# Joy2PS2_mini_v3.net
KiCad netlist of a schematic drawn in EAGLE
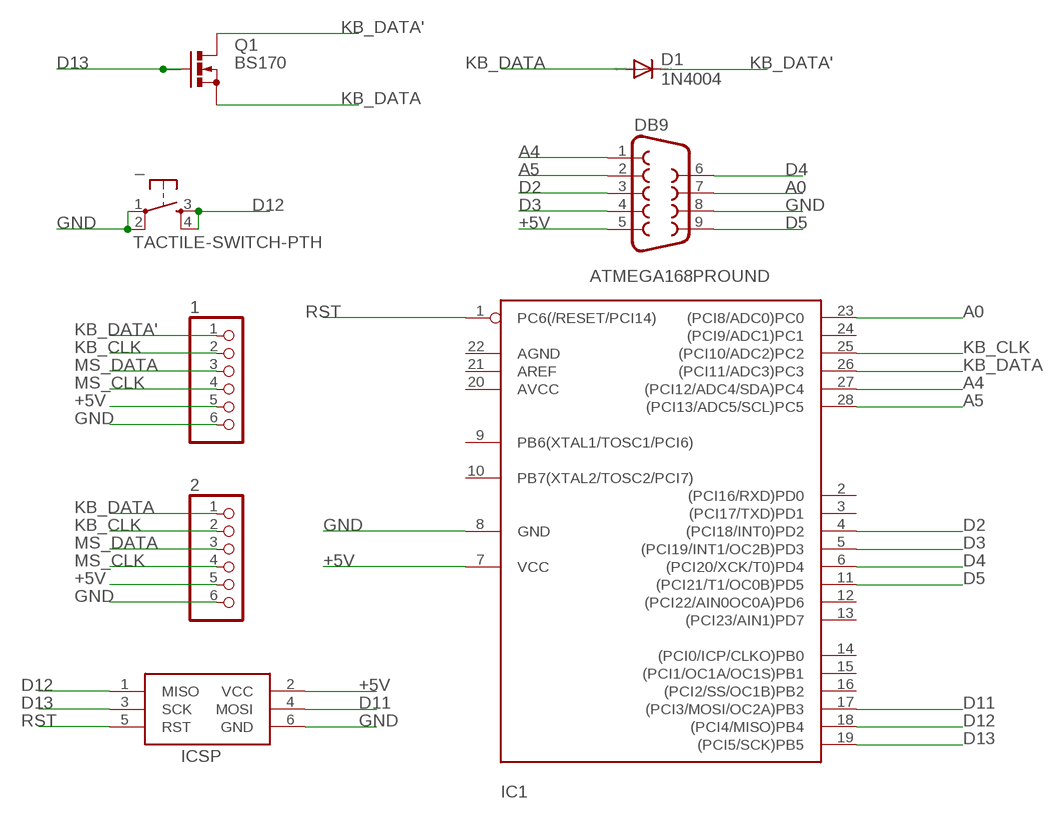
[diagram p0: schematic, sheet 1]

(export (version "E")
  (design (tool "Eeschema 10.0.6"))
  (components
    (comp (ref "1")
      (value "PINHD-1X6")
      (footprint "eagle-import:1X06")
      (libsource (lib "eagle-import") (part "PINHD-1X6"))
    )
    (comp (ref "2")
      (value "PINHD-1X6")
      (footprint "eagle-import:1X06")
      (libsource (lib "eagle-import") (part "PINHD-1X6"))
    )
    (comp (ref "D1")
      (value "1N4004")
      (footprint "eagle-import:DO41-10")
      (libsource (lib "eagle-import") (part "1N4004"))
    )
    (comp (ref "DB9")
      (value "DB9MALE")
      (footprint "eagle-import:DB9_MALE")
      (libsource (lib "eagle-import") (part "DB9MALE"))
    )
    (comp (ref "IC1")
      (value "ATMEGA168PROUND")
      (footprint "eagle-import:DIL28-3-ROUND")
      (libsource (lib "eagle-import") (part "ATMEGA168PROUND"))
    )
    (comp (ref "ICSP")
      (value "AVRISP-6")
      (footprint "eagle-import:AVRISP")
      (libsource (lib "eagle-import") (part "AVRISP-6"))
    )
    (comp (ref "Q1")
      (value "BS170")
      (footprint "eagle-import:SOT54E")
      (libsource (lib "eagle-import") (part "BS170"))
    )
    (comp (ref "_")
      (value "TACTILE-SWITCH-PTH")
      (footprint "eagle-import:TAC-SWITCH-PTH")
      (libsource (lib "eagle-import") (part "TACTILE-SWITCH-PTH"))
    )
  )
  (nets
    (net (code "1") (name "/+5V") (class "Default")
      (node (ref "1") (pin "5") (pinfunction "5_5") (pintype "passive"))
      (node (ref "2") (pin "5") (pinfunction "5_5") (pintype "passive"))
      (node (ref "DB9") (pin "5") (pinfunction "5_5") (pintype "passive"))
      (node (ref "IC1") (pin "7") (pinfunction "VCC_7") (pintype "bidirectional"))
      (node (ref "ICSP") (pin "2") (pinfunction "VCC_2") (pintype "power_in"))
    )
    (net (code "2") (name "/A0") (class "Default")
      (node (ref "DB9") (pin "7") (pinfunction "7_7") (pintype "passive"))
      (node (ref "IC1") (pin "23") (pinfunction "(PCI8/ADC0)PC0_23") (pintype "bidirectional"))
    )
    (net (code "3") (name "/A4") (class "Default")
      (node (ref "DB9") (pin "1") (pinfunction "1_1") (pintype "passive"))
      (node (ref "IC1") (pin "27") (pinfunction "(PCI12/ADC4/SDA)PC4_27") (pintype "bidirectional"))
    )
    (net (code "4") (name "/A5") (class "Default")
      (node (ref "DB9") (pin "2") (pinfunction "2_2") (pintype "passive"))
      (node (ref "IC1") (pin "28") (pinfunction "(PCI13/ADC5/SCL)PC5_28") (pintype "bidirectional"))
    )
    (net (code "5") (name "/D2") (class "Default")
      (node (ref "DB9") (pin "3") (pinfunction "3_3") (pintype "passive"))
      (node (ref "IC1") (pin "4") (pinfunction "(PCI18/INT0)PD2_4") (pintype "bidirectional"))
    )
    (net (code "6") (name "/D3") (class "Default")
      (node (ref "DB9") (pin "4") (pinfunction "4_4") (pintype "passive"))
      (node (ref "IC1") (pin "5") (pinfunction "(PCI19/INT1/OC2B)PD3_5") (pintype "bidirectional"))
    )
    (net (code "7") (name "/D4") (class "Default")
      (node (ref "DB9") (pin "6") (pinfunction "6_6") (pintype "passive"))
      (node (ref "IC1") (pin "6") (pinfunction "(PCI20/XCK/T0)PD4_6") (pintype "bidirectional"))
    )
    (net (code "8") (name "/D5") (class "Default")
      (node (ref "DB9") (pin "9") (pinfunction "9_9") (pintype "passive"))
      (node (ref "IC1") (pin "11") (pinfunction "(PCI21/T1/OC0B)PD5_11") (pintype "bidirectional"))
    )
    (net (code "9") (name "/D11") (class "Default")
      (node (ref "IC1") (pin "17") (pinfunction "(PCI3/MOSI/OC2A)PB3_17") (pintype "bidirectional"))
      (node (ref "ICSP") (pin "4") (pinfunction "MOSI_4") (pintype "output"))
    )
    (net (code "10") (name "/D12") (class "Default")
      (node (ref "IC1") (pin "18") (pinfunction "(PCI4/MISO)PB4_18") (pintype "bidirectional"))
      (node (ref "ICSP") (pin "1") (pinfunction "MISO_1") (pintype "input"))
      (node (ref "_") (pin "3") (pinfunction "3_3") (pintype "passive"))
      (node (ref "_") (pin "4") (pinfunction "4_4") (pintype "passive"))
    )
    (net (code "11") (name "/D13") (class "Default")
      (node (ref "IC1") (pin "19") (pinfunction "(PCI5/SCK)PB5_19") (pintype "bidirectional"))
      (node (ref "ICSP") (pin "3") (pinfunction "SCK_3") (pintype "output"))
      (node (ref "Q1") (pin "G") (pinfunction "G_G") (pintype "passive"))
    )
    (net (code "12") (name "/GND") (class "Default")
      (node (ref "1") (pin "6") (pinfunction "6_6") (pintype "passive"))
      (node (ref "2") (pin "6") (pinfunction "6_6") (pintype "passive"))
      (node (ref "DB9") (pin "8") (pinfunction "8_8") (pintype "passive"))
      (node (ref "IC1") (pin "8") (pinfunction "GND_8") (pintype "bidirectional"))
      (node (ref "ICSP") (pin "6") (pinfunction "GND_6") (pintype "power_in"))
      (node (ref "_") (pin "1") (pinfunction "1_1") (pintype "passive"))
      (node (ref "_") (pin "2") (pinfunction "2_2") (pintype "passive"))
    )
    (net (code "13") (name "/KB_CLK") (class "Default")
      (node (ref "1") (pin "2") (pinfunction "2_2") (pintype "passive"))
      (node (ref "2") (pin "2") (pinfunction "2_2") (pintype "passive"))
      (node (ref "IC1") (pin "25") (pinfunction "(PCI10/ADC2)PC2_25") (pintype "bidirectional"))
    )
    (net (code "14") (name "/KB_DATA") (class "Default")
      (node (ref "2") (pin "1") (pinfunction "1_1") (pintype "passive"))
      (node (ref "D1") (pin "A") (pinfunction "A_A") (pintype "passive"))
      (node (ref "IC1") (pin "26") (pinfunction "(PCI11/ADC3)PC3_26") (pintype "bidirectional"))
      (node (ref "Q1") (pin "S") (pinfunction "S_S") (pintype "passive"))
    )
    (net (code "15") (name "/KB_DATA'") (class "Default")
      (node (ref "1") (pin "1") (pinfunction "1_1") (pintype "passive"))
      (node (ref "D1") (pin "C") (pinfunction "C_C") (pintype "passive"))
      (node (ref "Q1") (pin "D") (pinfunction "D_D") (pintype "passive"))
    )
    (net (code "16") (name "/MS_CLK") (class "Default")
      (node (ref "1") (pin "4") (pinfunction "4_4") (pintype "passive"))
      (node (ref "2") (pin "4") (pinfunction "4_4") (pintype "passive"))
    )
    (net (code "17") (name "/MS_DATA") (class "Default")
      (node (ref "1") (pin "3") (pinfunction "3_3") (pintype "passive"))
      (node (ref "2") (pin "3") (pinfunction "3_3") (pintype "passive"))
    )
    (net (code "18") (name "/RST") (class "Default")
      (node (ref "IC1") (pin "1") (pinfunction "PC6(/RESET/PCI14)_1") (pintype "bidirectional"))
      (node (ref "ICSP") (pin "5") (pinfunction "RST_5") (pintype "output"))
    )
    (net (code "19") (name "unconnected-(IC1-(PCI0{slash}ICP{slash}CLKO)PB0-Pad14)") (class "Default")
      (node (ref "IC1") (pin "14") (pinfunction "(PCI0/ICP/CLKO)PB0_14") (pintype "bidirectional"))
    )
    (net (code "20") (name "unconnected-(IC1-(PCI1{slash}OC1A{slash}OC1S)PB1-Pad15)") (class "Default")
      (node (ref "IC1") (pin "15") (pinfunction "(PCI1/OC1A/OC1S)PB1_15") (pintype "bidirectional"))
    )
    (net (code "21") (name "unconnected-(IC1-(PCI2{slash}SS{slash}OC1B)PB2-Pad16)") (class "Default")
      (node (ref "IC1") (pin "16") (pinfunction "(PCI2/SS/OC1B)PB2_16") (pintype "bidirectional"))
    )
    (net (code "22") (name "unconnected-(IC1-(PCI9{slash}ADC1)PC1-Pad24)") (class "Default")
      (node (ref "IC1") (pin "24") (pinfunction "(PCI9/ADC1)PC1_24") (pintype "bidirectional"))
    )
    (net (code "23") (name "unconnected-(IC1-(PCI16{slash}RXD)PD0-Pad2)") (class "Default")
      (node (ref "IC1") (pin "2") (pinfunction "(PCI16/RXD)PD0_2") (pintype "bidirectional"))
    )
    (net (code "24") (name "unconnected-(IC1-(PCI17{slash}TXD)PD1-Pad3)") (class "Default")
      (node (ref "IC1") (pin "3") (pinfunction "(PCI17/TXD)PD1_3") (pintype "bidirectional"))
    )
    (net (code "25") (name "unconnected-(IC1-(PCI22{slash}AIN0OC0A)PD6-Pad12)") (class "Default")
      (node (ref "IC1") (pin "12") (pinfunction "(PCI22/AIN0OC0A)PD6_12") (pintype "bidirectional"))
    )
    (net (code "26") (name "unconnected-(IC1-(PCI23{slash}AIN1)PD7-Pad13)") (class "Default")
      (node (ref "IC1") (pin "13") (pinfunction "(PCI23/AIN1)PD7_13") (pintype "bidirectional"))
    )
    (net (code "27") (name "unconnected-(IC1-AGND-Pad22)") (class "Default")
      (node (ref "IC1") (pin "22") (pinfunction "AGND_22") (pintype "bidirectional"))
    )
    (net (code "28") (name "unconnected-(IC1-AREF-Pad21)") (class "Default")
      (node (ref "IC1") (pin "21") (pinfunction "AREF_21") (pintype "bidirectional"))
    )
    (net (code "29") (name "unconnected-(IC1-AVCC-Pad20)") (class "Default")
      (node (ref "IC1") (pin "20") (pinfunction "AVCC_20") (pintype "bidirectional"))
    )
    (net (code "30") (name "unconnected-(IC1-PB6(XTAL1{slash}TOSC1{slash}PCI6)-Pad9)") (class "Default")
      (node (ref "IC1") (pin "9") (pinfunction "PB6(XTAL1/TOSC1/PCI6)_9") (pintype "bidirectional"))
    )
    (net (code "31") (name "unconnected-(IC1-PB7(XTAL2{slash}TOSC2{slash}PCI7)-Pad10)") (class "Default")
      (node (ref "IC1") (pin "10") (pinfunction "PB7(XTAL2/TOSC2/PCI7)_10") (pintype "bidirectional"))
    )
  )
)
